# power-supplies.net
KiCad netlist of a schematic drawn in Altium Designer
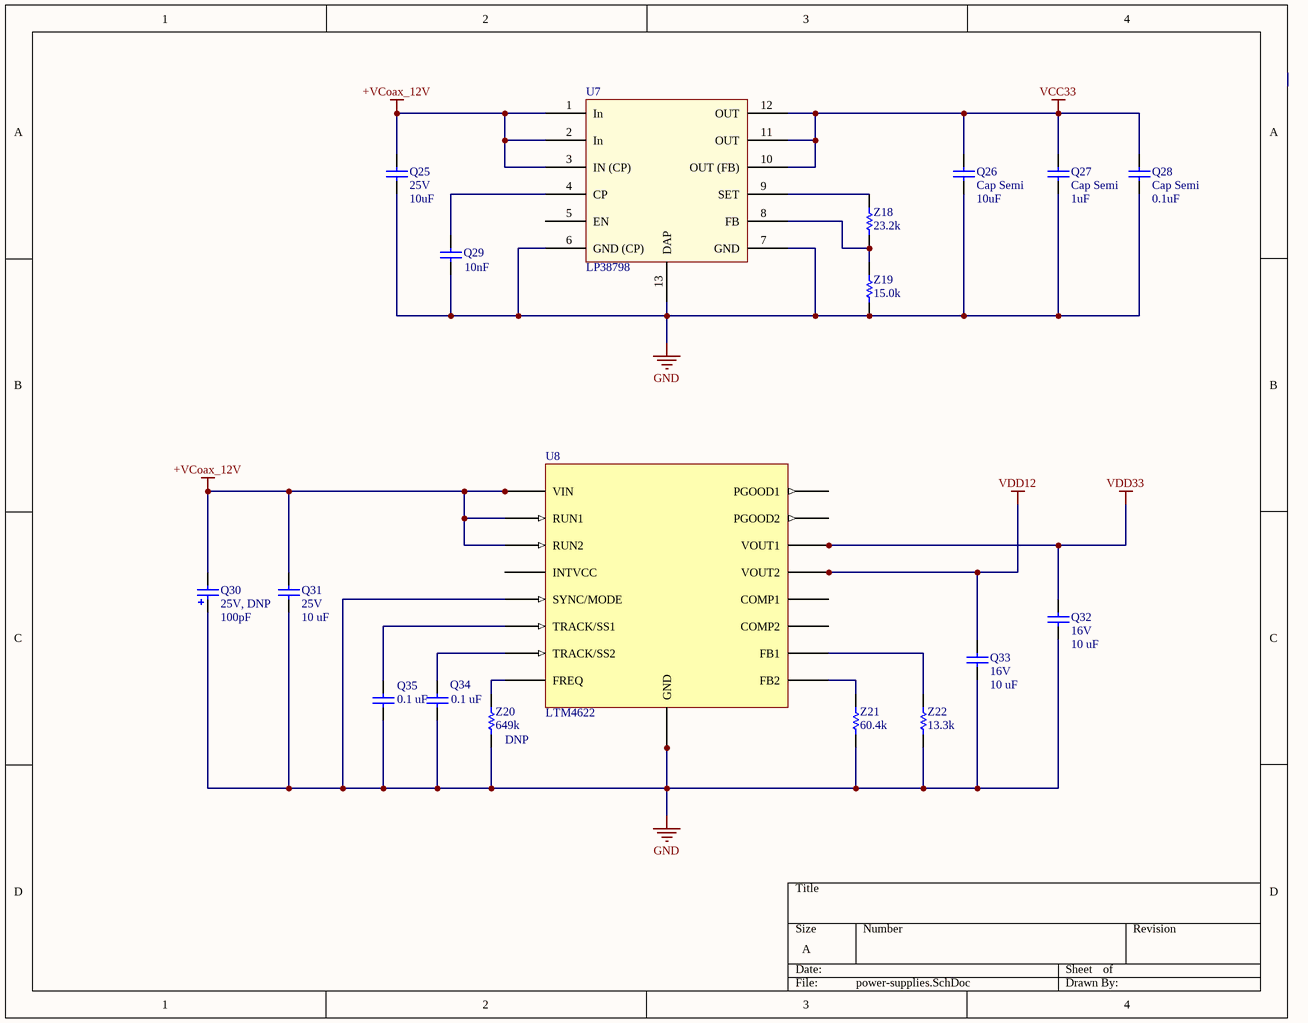
[diagram p0: power-supplies.SchDoc]

(export (version "E")
  (design (tool "Eeschema 10.0.6"))
  (components
    (comp (ref "Q25")
      (value "25V")
      (footprint "C1206")
      (description "Capacitor (Semiconductor SIM Model)")
      (fields (field (name "ALTIUM_VALUE") "10uF") (field (name "PUBLISHER") "Altium Limited"))
      (libsource (lib "Miscellaneous Devices") (part "Cap Semi"))
    )
    (comp (ref "Q26")
      (value "Cap Semi")
      (footprint "Cap-0603")
      (description "Capacitor (Semiconductor SIM Model)")
      (fields (field (name "ALTIUM_VALUE") "10uF") (field (name "PUBLISHER") "Altium Limited"))
      (libsource (lib "Miscellaneous Devices") (part "Cap Semi"))
    )
    (comp (ref "Q27")
      (value "Cap Semi")
      (footprint "Cap-0603")
      (description "Capacitor (Semiconductor SIM Model)")
      (fields (field (name "ALTIUM_VALUE") "1uF") (field (name "PUBLISHER") "Altium Limited"))
      (libsource (lib "Miscellaneous Devices") (part "Cap Semi"))
    )
    (comp (ref "Q28")
      (value "Cap Semi")
      (footprint "Cap-0603")
      (description "Capacitor (Semiconductor SIM Model)")
      (fields (field (name "ALTIUM_VALUE") "0.1uF") (field (name "PUBLISHER") "Altium Limited"))
      (libsource (lib "Miscellaneous Devices") (part "Cap Semi"))
    )
    (comp (ref "Q29")
      (value "10nF")
      (footprint "0402")
      (description "Capacitor (Semiconductor SIM Model)")
      (fields (field (name "PUBLISHER") "Altium Limited"))
      (libsource (lib "Miscellaneous Devices") (part "Cap Semi"))
    )
    (comp (ref "Q30")
      (value "25V, DNP")
      (footprint "C0805")
      (description "Polarized Capacitor (Surface Mount)")
      (fields (field (name "ALTIUM_VALUE") "100pF") (field (name "PUBLISHER") "Altium Limited"))
      (libsource (lib "Miscellaneous Devices") (part "Cap Pol3"))
    )
    (comp (ref "Q31")
      (value "25V")
      (footprint "C1206")
      (description "Capacitor (Semiconductor SIM Model)")
      (fields
        (field (name "ALTIUM_VALUE") "10 uF")
        (field (name "VOLTAGE") "25 V")
        (field (name "PUBLISHER") "Altium Limited")
      )
      (libsource (lib "Miscellaneous Devices") (part "Cap Semi"))
    )
    (comp (ref "Q32")
      (value "16V")
      (footprint "C1206")
      (description "Capacitor (Semiconductor SIM Model)")
      (fields
        (field (name "ALTIUM_VALUE") "10 uF")
        (field (name "VOLTAGE") "16 V")
        (field (name "PUBLISHER") "Altium Limited")
      )
      (libsource (lib "Miscellaneous Devices") (part "Cap Semi"))
    )
    (comp (ref "Q33")
      (value "16V")
      (footprint "C1206")
      (description "Capacitor (Semiconductor SIM Model)")
      (fields
        (field (name "ALTIUM_VALUE") "10 uF")
        (field (name "VOLTAGE") "16 V")
        (field (name "PUBLISHER") "Altium Limited")
      )
      (libsource (lib "Miscellaneous Devices") (part "Cap Semi"))
    )
    (comp (ref "Q34")
      (value "0.1 uF")
      (footprint "C1206")
      (description "Capacitor (Semiconductor SIM Model)")
      (fields
        (field (name "VOLTAGE") "25 V")
        (field (name "Comment") "25V")
        (field (name "PUBLISHER") "Altium Limited")
      )
      (libsource (lib "Miscellaneous Devices") (part "Cap Semi"))
    )
    (comp (ref "Q35")
      (value "0.1 uF")
      (footprint "C1206")
      (description "Capacitor (Semiconductor SIM Model)")
      (fields
        (field (name "VOLTAGE") "25 V")
        (field (name "Comment") "25V")
        (field (name "PUBLISHER") "Altium Limited")
      )
      (libsource (lib "Miscellaneous Devices") (part "Cap Semi"))
    )
    (comp (ref "U7")
      (value "LP38798")
      (footprint "DFN12")
      (description "Low Noise Positive LDO")
      (libsource (lib "jonnew") (part "Component_1"))
    )
    (comp (ref "U8") (value "LTM4622") (footprint "LGA5x5") (libsource (lib "jonnew") (part "LTM4622")))
    (comp (ref "Z18")
      (value "23.2k")
      (footprint "Res_0402")
      (description "Resistor")
      (fields (field (name "Comment") "Res1") (field (name "PUBLISHER") "Altium Limited"))
      (libsource (lib "Miscellaneous Devices") (part "Res1"))
    )
    (comp (ref "Z19")
      (value "15.0k")
      (footprint "Res_0402")
      (description "Resistor")
      (fields (field (name "Comment") "Res1") (field (name "PUBLISHER") "Altium Limited"))
      (libsource (lib "Miscellaneous Devices") (part "Res1"))
    )
    (comp (ref "Z20")
      (value "DNP")
      (footprint "Res_0402")
      (description "Resistor")
      (fields (field (name "ALTIUM_VALUE") "649k") (field (name "PUBLISHER") "Altium Limited"))
      (libsource (lib "Miscellaneous Devices") (part "Res1"))
    )
    (comp (ref "Z21")
      (value "60.4k")
      (footprint "Res_0402")
      (description "Resistor")
      (fields (field (name "Comment") "649k (DNP)") (field (name "PUBLISHER") "Altium Limited"))
      (libsource (lib "Miscellaneous Devices") (part "Res1"))
    )
    (comp (ref "Z22")
      (value "13.3k")
      (footprint "Res_0402")
      (description "Resistor")
      (fields (field (name "PUBLISHER") "Altium Limited"))
      (libsource (lib "Miscellaneous Devices") (part "Res1"))
    )
  )
  (nets
    (net (code "1") (name "+VCoax_12V") (class "Default")
      (node (ref "Q25") (pin "2") (pinfunction "2_2") (pintype "passive"))
      (node (ref "Q30") (pin "2") (pinfunction "2_2") (pintype "passive"))
      (node (ref "Q31") (pin "2") (pinfunction "2_2") (pintype "passive"))
      (node (ref "U7") (pin "1") (pinfunction "In_1") (pintype "power_in"))
      (node (ref "U7") (pin "2") (pinfunction "In_2") (pintype "power_in"))
      (node (ref "U7") (pin "3") (pinfunction "IN_(CP)_3") (pintype "power_in"))
      (node (ref "U8") (pin "A2") (pinfunction "VIN_A2") (pintype "power_in"))
      (node (ref "U8") (pin "B2") (pinfunction "RUN2_B2") (pintype "input"))
      (node (ref "U8") (pin "B3") (pinfunction "VIN_B3") (pintype "passive"))
      (node (ref "U8") (pin "D2") (pinfunction "RUN1_D2") (pintype "input"))
      (node (ref "U8") (pin "D3") (pinfunction "VIN_D3") (pintype "passive"))
      (node (ref "U8") (pin "E2") (pinfunction "VIN_E2") (pintype "passive"))
    )
    (net (code "2") (name "GND") (class "Default")
      (node (ref "Q25") (pin "1") (pinfunction "1_1") (pintype "passive"))
      (node (ref "Q26") (pin "1") (pinfunction "1_1") (pintype "passive"))
      (node (ref "Q27") (pin "1") (pinfunction "1_1") (pintype "passive"))
      (node (ref "Q28") (pin "1") (pinfunction "1_1") (pintype "passive"))
      (node (ref "Q29") (pin "1") (pinfunction "1_1") (pintype "passive"))
      (node (ref "Q30") (pin "1") (pinfunction "1_1") (pintype "passive"))
      (node (ref "Q31") (pin "1") (pinfunction "1_1") (pintype "passive"))
      (node (ref "Q32") (pin "1") (pinfunction "1_1") (pintype "passive"))
      (node (ref "Q33") (pin "1") (pinfunction "1_1") (pintype "passive"))
      (node (ref "Q34") (pin "1") (pinfunction "1_1") (pintype "passive"))
      (node (ref "Q35") (pin "1") (pinfunction "1_1") (pintype "passive"))
      (node (ref "U7") (pin "13") (pinfunction "DAP_13") (pintype "passive"))
      (node (ref "U7") (pin "6") (pinfunction "GND_(CP)_6") (pintype "passive"))
      (node (ref "U7") (pin "7") (pinfunction "GND_7") (pintype "power_in"))
      (node (ref "U8") (pin "B5") (pinfunction "GND_B5") (pintype "passive"))
      (node (ref "U8") (pin "C1") (pinfunction "GND_C1") (pintype "power_in"))
      (node (ref "U8") (pin "C2") (pinfunction "GND_C2") (pintype "passive"))
      (node (ref "U8") (pin "C5") (pinfunction "SYNC/MODE_C5") (pintype "input"))
      (node (ref "U8") (pin "D5") (pinfunction "GND_D5") (pintype "passive"))
      (node (ref "Z19") (pin "2") (pinfunction "2_2") (pintype "passive"))
      (node (ref "Z20") (pin "2") (pinfunction "2_2") (pintype "passive"))
      (node (ref "Z21") (pin "2") (pinfunction "2_2") (pintype "passive"))
      (node (ref "Z22") (pin "2") (pinfunction "2_2") (pintype "passive"))
    )
    (net (code "3") (name "Net-(U7-CP)") (class "Default")
      (node (ref "Q29") (pin "2") (pinfunction "2_2") (pintype "passive"))
      (node (ref "U7") (pin "4") (pinfunction "CP_4") (pintype "passive"))
    )
    (net (code "4") (name "Net-(U7-FB)") (class "Default")
      (node (ref "U7") (pin "8") (pinfunction "FB_8") (pintype "passive"))
      (node (ref "Z18") (pin "2") (pinfunction "2_2") (pintype "passive"))
      (node (ref "Z19") (pin "1") (pinfunction "1_1") (pintype "passive"))
    )
    (net (code "5") (name "Net-(U7-SET)") (class "Default")
      (node (ref "U7") (pin "9") (pinfunction "SET_9") (pintype "passive"))
      (node (ref "Z18") (pin "1") (pinfunction "1_1") (pintype "passive"))
    )
    (net (code "6") (name "Net-(U8-FB1)") (class "Default")
      (node (ref "U8") (pin "E4") (pinfunction "FB1_E4") (pintype "passive"))
      (node (ref "Z22") (pin "1") (pinfunction "1_1") (pintype "passive"))
    )
    (net (code "7") (name "Net-(U8-FB2)") (class "Default")
      (node (ref "U8") (pin "A4") (pinfunction "FB2_A4") (pintype "passive"))
      (node (ref "Z21") (pin "1") (pinfunction "1_1") (pintype "passive"))
    )
    (net (code "8") (name "Net-(U8-FREQ)") (class "Default")
      (node (ref "U8") (pin "C4") (pinfunction "FREQ_C4") (pintype "passive"))
      (node (ref "Z20") (pin "1") (pinfunction "1_1") (pintype "passive"))
    )
    (net (code "9") (name "Net-(U8-TRACK{slash}SS1)") (class "Default")
      (node (ref "Q35") (pin "2") (pinfunction "2_2") (pintype "passive"))
      (node (ref "U8") (pin "E5") (pinfunction "TRACK/SS1_E5") (pintype "input"))
    )
    (net (code "10") (name "Net-(U8-TRACK{slash}SS2)") (class "Default")
      (node (ref "Q34") (pin "2") (pinfunction "2_2") (pintype "passive"))
      (node (ref "U8") (pin "A3") (pinfunction "TRACK/SS2_A3") (pintype "input"))
    )
    (net (code "11") (name "VCC33") (class "Default")
      (node (ref "Q26") (pin "2") (pinfunction "2_2") (pintype "passive"))
      (node (ref "Q27") (pin "2") (pinfunction "2_2") (pintype "passive"))
      (node (ref "Q28") (pin "2") (pinfunction "2_2") (pintype "passive"))
      (node (ref "U7") (pin "10") (pinfunction "OUT_(FB)_10") (pintype "passive"))
      (node (ref "U7") (pin "11") (pinfunction "OUT_11") (pintype "power_in"))
      (node (ref "U7") (pin "12") (pinfunction "OUT_12") (pintype "power_in"))
    )
    (net (code "12") (name "VDD12") (class "Default")
      (node (ref "Q33") (pin "2") (pinfunction "2_2") (pintype "passive"))
      (node (ref "U8") (pin "A1") (pinfunction "VOUT2_A1") (pintype "power_in"))
      (node (ref "U8") (pin "B1") (pinfunction "VOUT2_B1") (pintype "passive"))
    )
    (net (code "13") (name "VDD33") (class "Default")
      (node (ref "Q32") (pin "2") (pinfunction "2_2") (pintype "passive"))
      (node (ref "U8") (pin "D1") (pinfunction "VOUT1_D1") (pintype "power_in"))
      (node (ref "U8") (pin "E1") (pinfunction "VOUT1_E1") (pintype "passive"))
    )
    (net (code "14") (name "unconnected-(U7-EN-Pad5)") (class "Default")
      (node (ref "U7") (pin "5") (pinfunction "EN_5") (pintype "passive"))
    )
    (net (code "15") (name "unconnected-(U8-COMP1-PadE5)") (class "Default")
      (node (ref "U8") (pin "E5") (pinfunction "COMP1_E5") (pintype "passive"))
    )
    (net (code "16") (name "unconnected-(U8-COMP2-PadA5)") (class "Default")
      (node (ref "U8") (pin "A5") (pinfunction "COMP2_A5") (pintype "passive"))
    )
    (net (code "17") (name "unconnected-(U8-INTVCC-PadC3)") (class "Default")
      (node (ref "U8") (pin "C3") (pinfunction "INTVCC_C3") (pintype "passive"))
    )
    (net (code "18") (name "unconnected-(U8-PGOOD1-PadD4)") (class "Default")
      (node (ref "U8") (pin "D4") (pinfunction "PGOOD1_D4") (pintype "output"))
    )
    (net (code "19") (name "unconnected-(U8-PGOOD2-PadB4)") (class "Default")
      (node (ref "U8") (pin "B4") (pinfunction "PGOOD2_B4") (pintype "output"))
    )
  )
)
